# 1-Schematic_Levitator_v2.net
KiCad netlist of a schematic drawn in EasyEDA
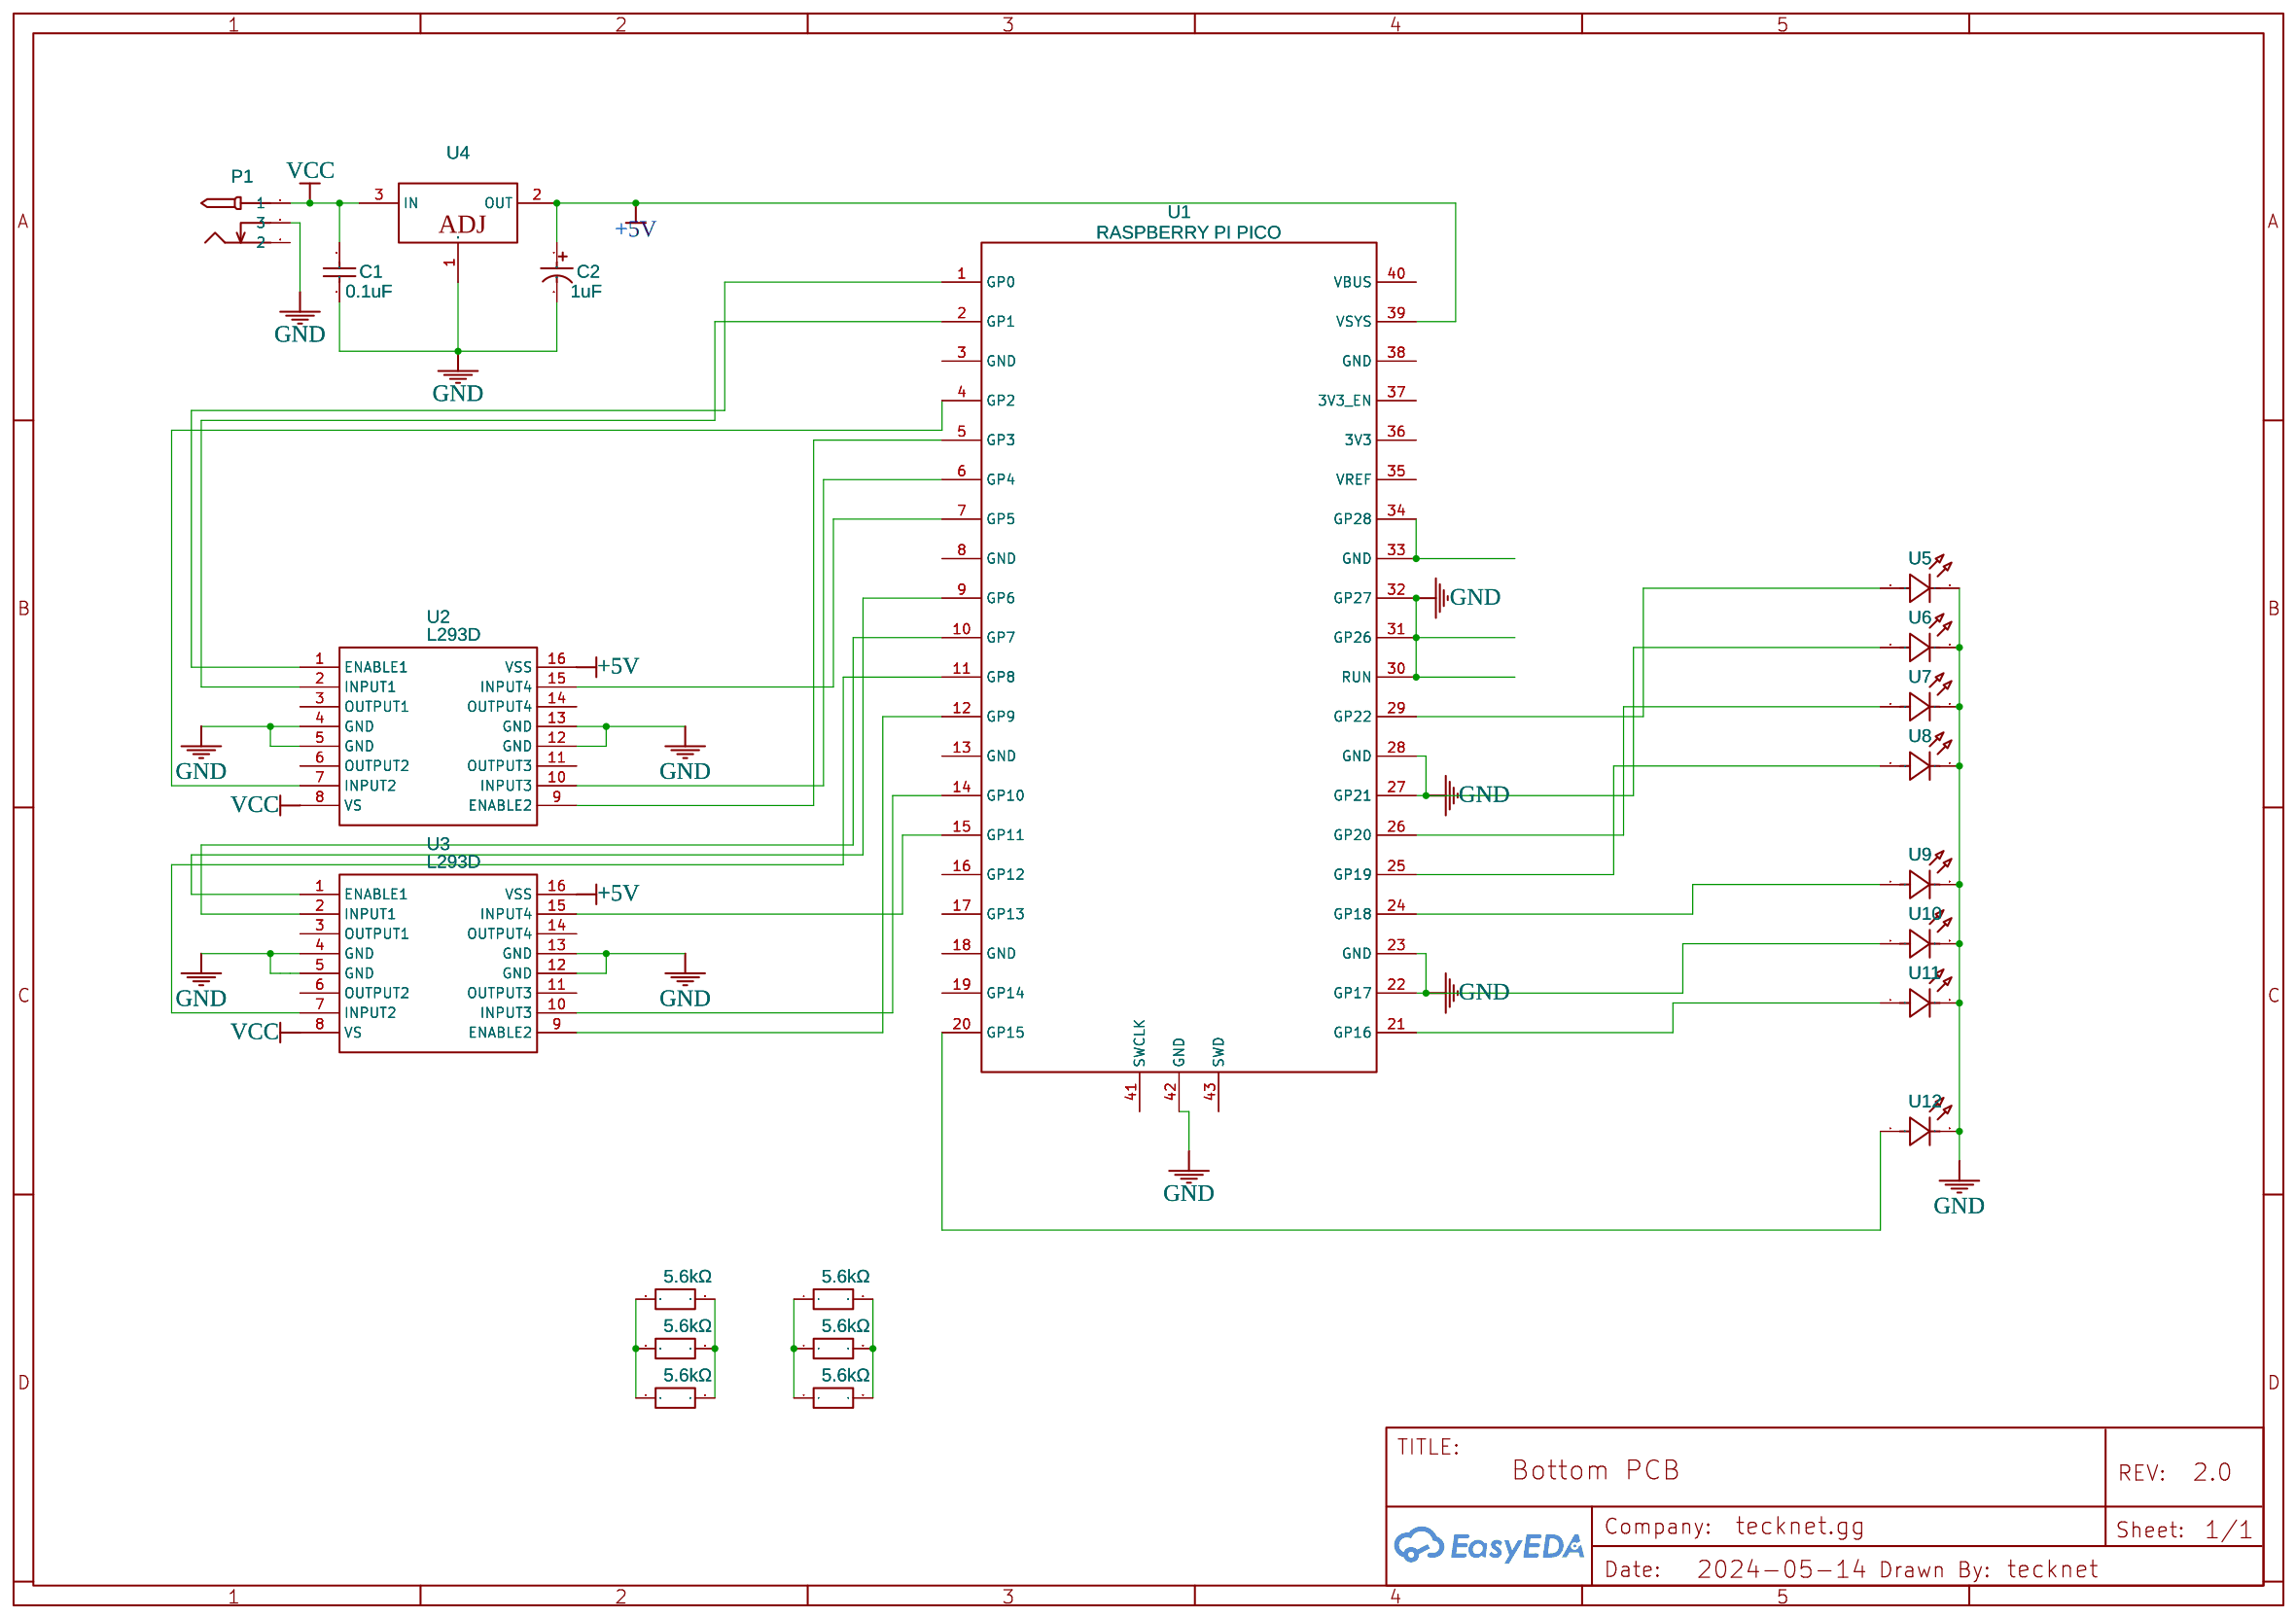
[diagram p0: Bottom PCB]
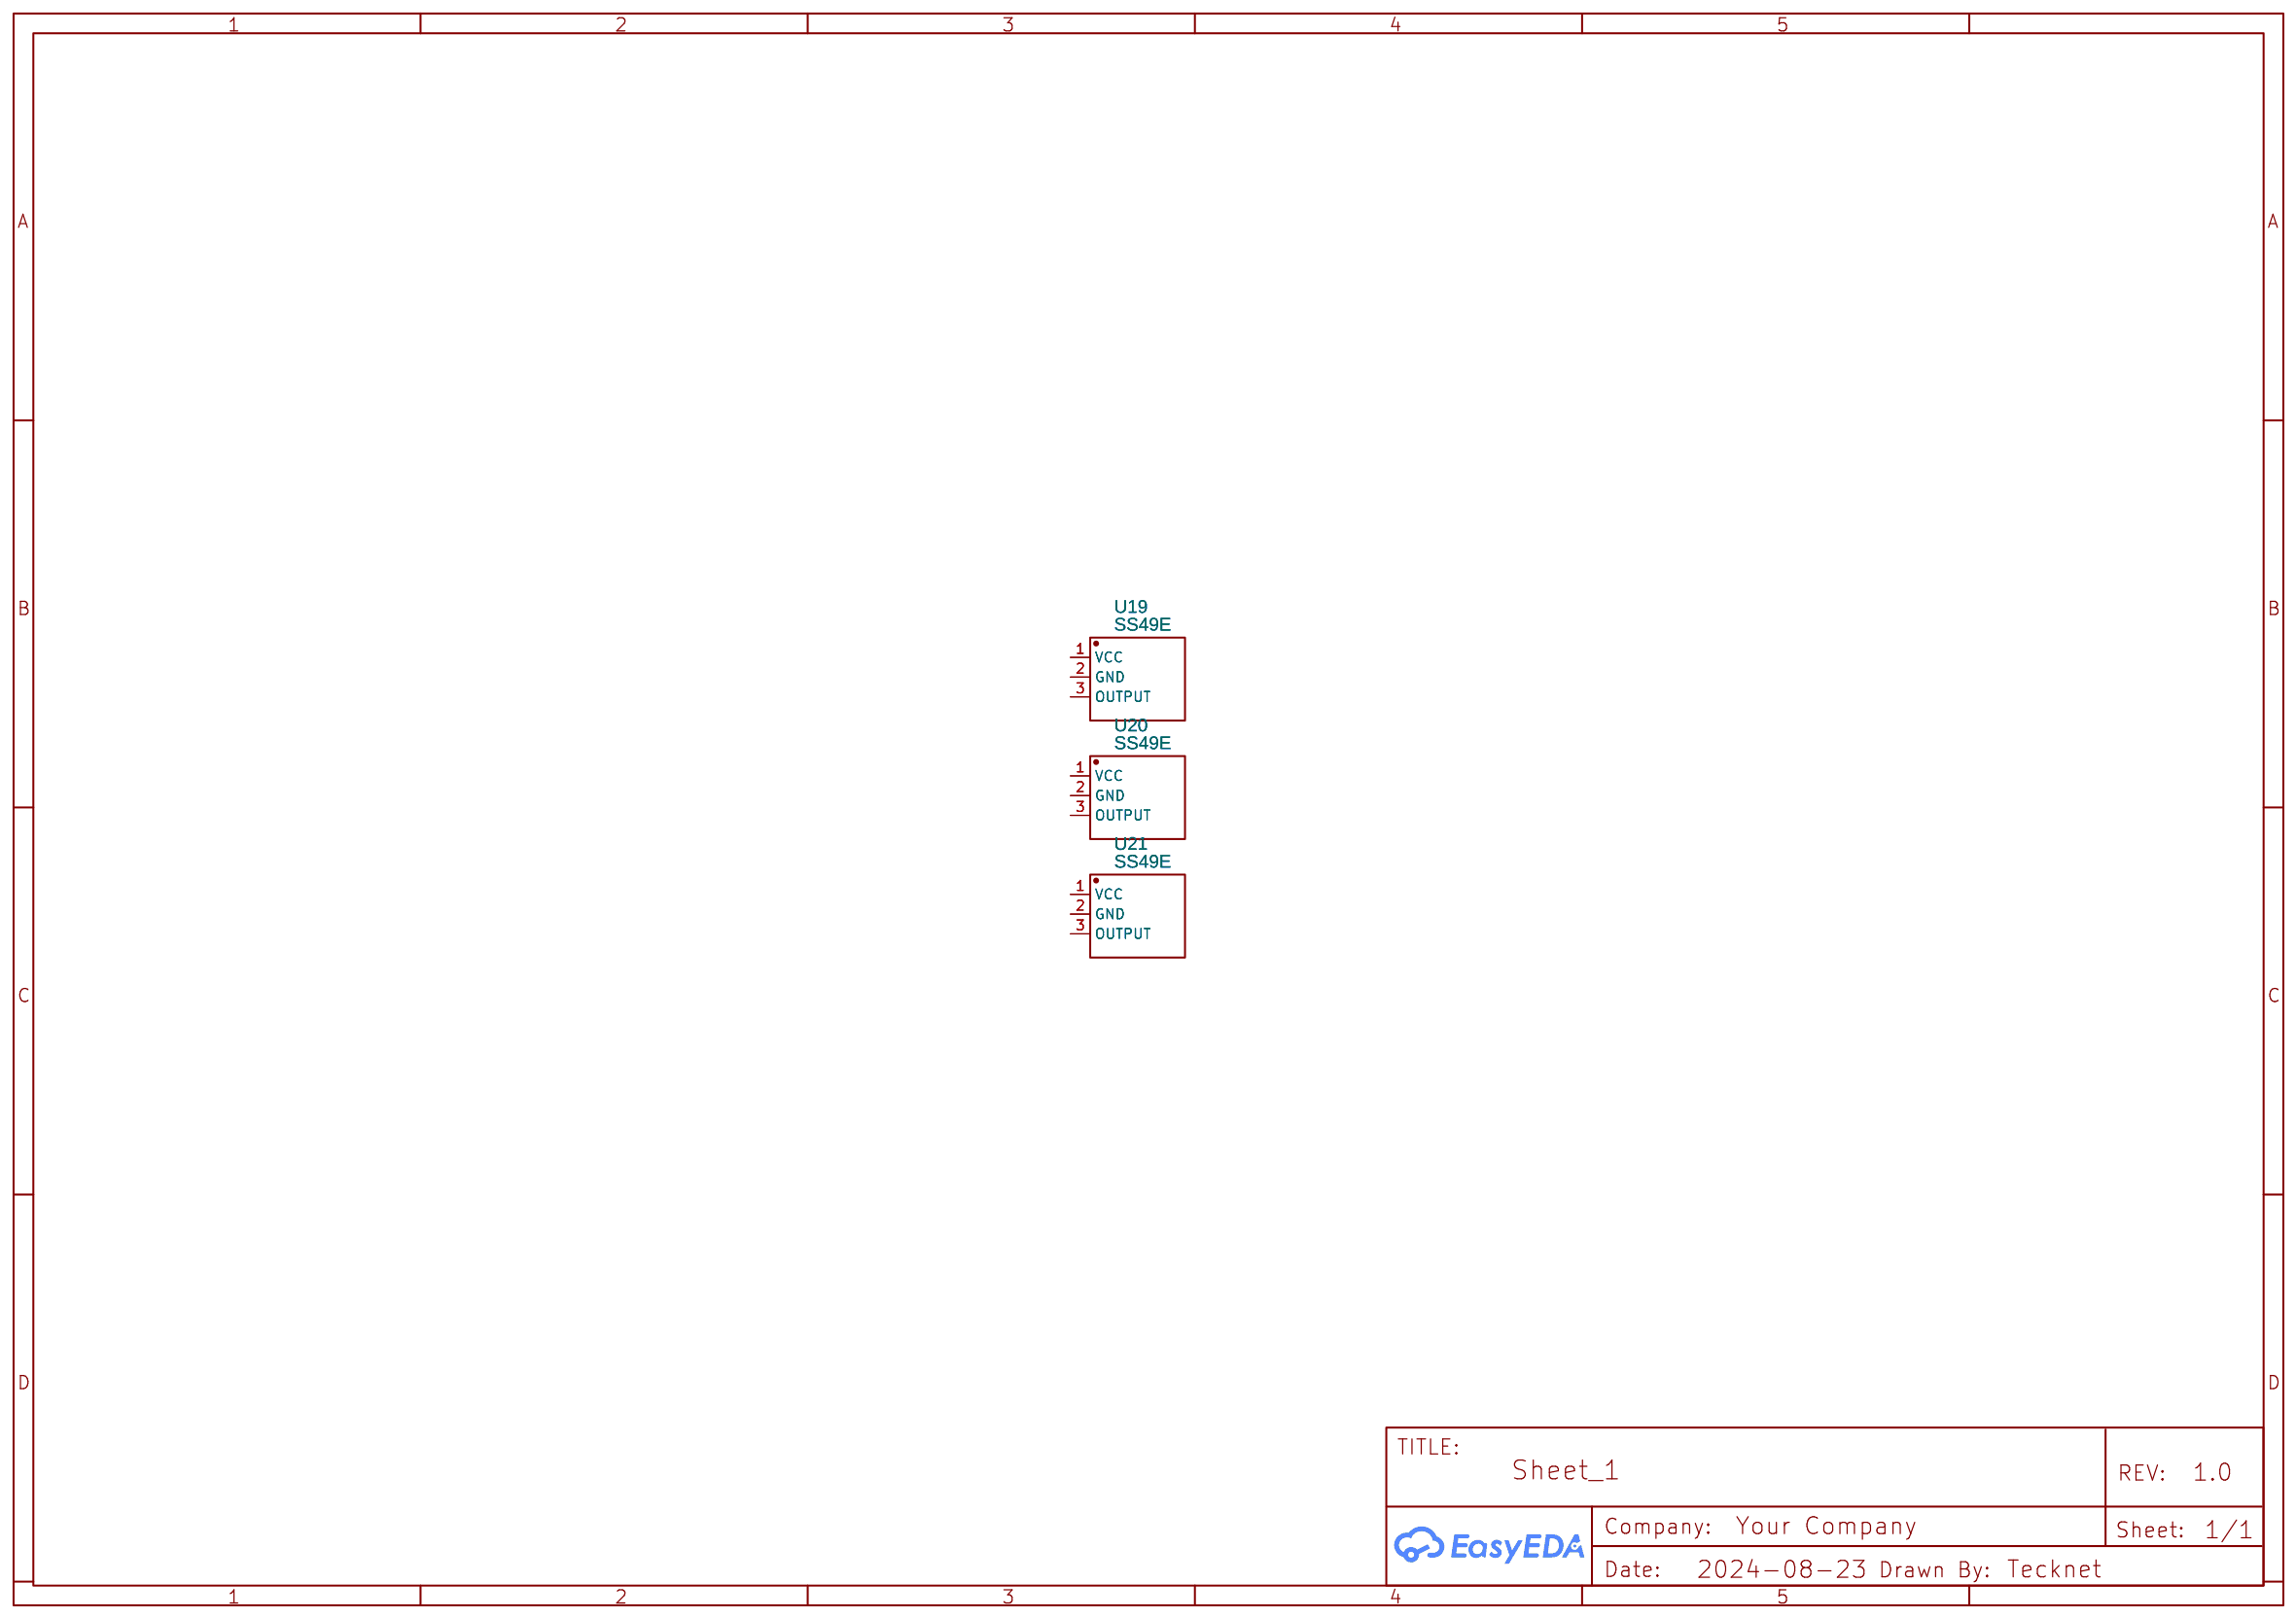
[diagram p1: Sheet_1]

(export (version "E")
  (design (tool "Eeschema 10.0.6"))
  (components
    (comp (ref "C1")
      (value "0.1uF")
      (fields (field (name "Manufacturer Part") "CT4-0805Y104M500") (field (name "Manufacturer") "LCSC"))
      (libsource (lib "") (part "CERAMIC CAPACITOR 100NF"))
    )
    (comp (ref "C2")
      (value "1uF")
      (fields
        (field (name "Manufacturer Part") "KM105M400E12RR0VH2FP0")
        (field (name "Manufacturer") "CX(承兴)")
      )
      (libsource (lib "") (part "1uF 400V 6.3*12"))
    )
    (comp (ref "P1") (value "BARREL POWER JACK 2.1MM") (libsource (lib "") (part "BARREL POWER JACK 2.1MM")))
    (comp (ref "U1")
      (value "RASPBERRY PI PICO")
      (fields (field (name "Manufacturer Part") "Raspberry Pi Pico"))
      (libsource (lib "") (part "RASPBERRY PI PICO"))
    )
    (comp (ref "U2")
      (value "L293D")
      (fields (field (name "Manufacturer") "ST(意法半导体)"))
      (libsource (lib "") (part "L293D"))
    )
    (comp (ref "U3")
      (value "L293D")
      (fields (field (name "Manufacturer") "ST(意法半导体)"))
      (libsource (lib "") (part "L293D"))
    )
    (comp (ref "U4")
      (value "LM317T_C2976492")
      (fields (field (name "Manufacturer Part") "LM317T") (field (name "Manufacturer") "ISC(无锡固电)"))
      (libsource (lib "") (part "LM317T_C2976492"))
    )
    (comp (ref "U5") (value "L240CTZ0G3MM") (libsource (lib "") (part "L240CTZ0G3MM")))
    (comp (ref "U6") (value "L240CTZ0G3MM") (libsource (lib "") (part "L240CTZ0G3MM")))
    (comp (ref "U7") (value "L240CTZ0G3MM") (libsource (lib "") (part "L240CTZ0G3MM")))
    (comp (ref "U8") (value "L240CTZ0G3MM") (libsource (lib "") (part "L240CTZ0G3MM")))
    (comp (ref "U9") (value "L240CTZ0G3MM") (libsource (lib "") (part "L240CTZ0G3MM")))
    (comp (ref "U10") (value "L240CTZ0G3MM") (libsource (lib "") (part "L240CTZ0G3MM")))
    (comp (ref "U11") (value "L240CTZ0G3MM") (libsource (lib "") (part "L240CTZ0G3MM")))
    (comp (ref "U12") (value "L240CTZ0G3MM") (libsource (lib "") (part "L240CTZ0G3MM")))
    (comp (ref "U13")
      (value "5.6kΩ")
      (fields
        (field (name "Manufacturer Part") "CF14JT5K60")
        (field (name "Manufacturer") "SEI(Stackpole Electronics Inc.)")
      )
      (libsource (lib "") (part "CF14JT5K60"))
    )
    (comp (ref "U14")
      (value "5.6kΩ")
      (fields
        (field (name "Manufacturer Part") "CF14JT5K60")
        (field (name "Manufacturer") "SEI(Stackpole Electronics Inc.)")
      )
      (libsource (lib "") (part "CF14JT5K60"))
    )
    (comp (ref "U15")
      (value "5.6kΩ")
      (fields
        (field (name "Manufacturer Part") "CF14JT5K60")
        (field (name "Manufacturer") "SEI(Stackpole Electronics Inc.)")
      )
      (libsource (lib "") (part "CF14JT5K60"))
    )
    (comp (ref "U16")
      (value "5.6kΩ")
      (fields
        (field (name "Manufacturer Part") "CF14JT5K60")
        (field (name "Manufacturer") "SEI(Stackpole Electronics Inc.)")
      )
      (libsource (lib "") (part "CF14JT5K60"))
    )
    (comp (ref "U17")
      (value "5.6kΩ")
      (fields
        (field (name "Manufacturer Part") "CF14JT5K60")
        (field (name "Manufacturer") "SEI(Stackpole Electronics Inc.)")
      )
      (libsource (lib "") (part "CF14JT5K60"))
    )
    (comp (ref "U18")
      (value "5.6kΩ")
      (fields
        (field (name "Manufacturer Part") "CF14JT5K60")
        (field (name "Manufacturer") "SEI(Stackpole Electronics Inc.)")
      )
      (libsource (lib "") (part "CF14JT5K60"))
    )
    (comp (ref "U19")
      (value "SS49E")
      (fields (field (name "Manufacturer") "Honeywell(霍尼韦尔)"))
      (libsource (lib "") (part "SS49E"))
    )
    (comp (ref "U20")
      (value "SS49E")
      (fields (field (name "Manufacturer") "Honeywell(霍尼韦尔)"))
      (libsource (lib "") (part "SS49E"))
    )
    (comp (ref "U21")
      (value "SS49E")
      (fields (field (name "Manufacturer") "Honeywell(霍尼韦尔)"))
      (libsource (lib "") (part "SS49E"))
    )
  )
  (nets
    (net (code "1") (name "+5V") (class "Default")
      (node (ref "C2") (pin "1") (pinfunction "1_1") (pintype "input"))
      (node (ref "U1") (pin "39") (pinfunction "VSYS_39") (pintype "unspecified"))
      (node (ref "U2") (pin "16") (pinfunction "VSS_16") (pintype "unspecified"))
      (node (ref "U3") (pin "16") (pinfunction "VSS_16") (pintype "unspecified"))
      (node (ref "U4") (pin "2") (pinfunction "OUT_2") (pintype "passive"))
    )
    (net (code "2") (name "GND") (class "Default")
      (node (ref "C1") (pin "1") (pinfunction "1_1") (pintype "input"))
      (node (ref "C2") (pin "2") (pinfunction "2_2") (pintype "input"))
      (node (ref "P1") (pin "3") (pinfunction "3_3") (pintype "unspecified"))
      (node (ref "U1") (pin "22") (pinfunction "GP17_22") (pintype "unspecified"))
      (node (ref "U1") (pin "23") (pinfunction "GND_23") (pintype "unspecified"))
      (node (ref "U1") (pin "27") (pinfunction "GP21_27") (pintype "unspecified"))
      (node (ref "U1") (pin "28") (pinfunction "GND_28") (pintype "unspecified"))
      (node (ref "U1") (pin "30") (pinfunction "RUN_30") (pintype "unspecified"))
      (node (ref "U1") (pin "31") (pinfunction "GP26_31") (pintype "unspecified"))
      (node (ref "U1") (pin "32") (pinfunction "GP27_32") (pintype "unspecified"))
      (node (ref "U1") (pin "42") (pinfunction "GND_42") (pintype "unspecified"))
      (node (ref "U10") (pin "1") (pinfunction "A_1") (pintype "unspecified"))
      (node (ref "U10") (pin "2") (pinfunction "K_2") (pintype "unspecified"))
      (node (ref "U11") (pin "2") (pinfunction "K_2") (pintype "unspecified"))
      (node (ref "U12") (pin "2") (pinfunction "K_2") (pintype "unspecified"))
      (node (ref "U2") (pin "12") (pinfunction "GND_12") (pintype "unspecified"))
      (node (ref "U2") (pin "13") (pinfunction "GND_13") (pintype "unspecified"))
      (node (ref "U2") (pin "4") (pinfunction "GND_4") (pintype "unspecified"))
      (node (ref "U2") (pin "5") (pinfunction "GND_5") (pintype "unspecified"))
      (node (ref "U3") (pin "12") (pinfunction "GND_12") (pintype "unspecified"))
      (node (ref "U3") (pin "13") (pinfunction "GND_13") (pintype "unspecified"))
      (node (ref "U3") (pin "4") (pinfunction "GND_4") (pintype "unspecified"))
      (node (ref "U3") (pin "5") (pinfunction "GND_5") (pintype "unspecified"))
      (node (ref "U4") (pin "1") (pinfunction "ADJ_1") (pintype "unspecified"))
      (node (ref "U5") (pin "2") (pinfunction "K_2") (pintype "unspecified"))
      (node (ref "U6") (pin "1") (pinfunction "A_1") (pintype "unspecified"))
      (node (ref "U6") (pin "2") (pinfunction "K_2") (pintype "unspecified"))
      (node (ref "U7") (pin "2") (pinfunction "K_2") (pintype "unspecified"))
      (node (ref "U8") (pin "2") (pinfunction "K_2") (pintype "unspecified"))
      (node (ref "U9") (pin "2") (pinfunction "K_2") (pintype "unspecified"))
    )
    (net (code "3") (name "Net-(U1-GP0)") (class "Default")
      (node (ref "U1") (pin "1") (pinfunction "GP0_1") (pintype "unspecified"))
      (node (ref "U2") (pin "1") (pinfunction "ENABLE1_1") (pintype "unspecified"))
    )
    (net (code "4") (name "Net-(U1-GP1)") (class "Default")
      (node (ref "U1") (pin "2") (pinfunction "GP1_2") (pintype "unspecified"))
      (node (ref "U2") (pin "2") (pinfunction "INPUT1_2") (pintype "unspecified"))
    )
    (net (code "5") (name "Net-(U1-GP2)") (class "Default")
      (node (ref "U1") (pin "4") (pinfunction "GP2_4") (pintype "unspecified"))
      (node (ref "U2") (pin "7") (pinfunction "INPUT2_7") (pintype "unspecified"))
    )
    (net (code "6") (name "Net-(U1-GP3)") (class "Default")
      (node (ref "U1") (pin "5") (pinfunction "GP3_5") (pintype "unspecified"))
      (node (ref "U2") (pin "9") (pinfunction "ENABLE2_9") (pintype "unspecified"))
    )
    (net (code "7") (name "Net-(U1-GP4)") (class "Default")
      (node (ref "U1") (pin "6") (pinfunction "GP4_6") (pintype "unspecified"))
      (node (ref "U2") (pin "10") (pinfunction "INPUT3_10") (pintype "unspecified"))
    )
    (net (code "8") (name "Net-(U1-GP5)") (class "Default")
      (node (ref "U1") (pin "7") (pinfunction "GP5_7") (pintype "unspecified"))
      (node (ref "U2") (pin "15") (pinfunction "INPUT4_15") (pintype "unspecified"))
    )
    (net (code "9") (name "Net-(U1-GP6)") (class "Default")
      (node (ref "U1") (pin "9") (pinfunction "GP6_9") (pintype "unspecified"))
      (node (ref "U3") (pin "1") (pinfunction "ENABLE1_1") (pintype "unspecified"))
    )
    (net (code "10") (name "Net-(U1-GP7)") (class "Default")
      (node (ref "U1") (pin "10") (pinfunction "GP7_10") (pintype "unspecified"))
      (node (ref "U3") (pin "2") (pinfunction "INPUT1_2") (pintype "unspecified"))
    )
    (net (code "11") (name "Net-(U1-GP8)") (class "Default")
      (node (ref "U1") (pin "11") (pinfunction "GP8_11") (pintype "unspecified"))
      (node (ref "U3") (pin "7") (pinfunction "INPUT2_7") (pintype "unspecified"))
    )
    (net (code "12") (name "Net-(U1-GP9)") (class "Default")
      (node (ref "U1") (pin "12") (pinfunction "GP9_12") (pintype "unspecified"))
      (node (ref "U3") (pin "9") (pinfunction "ENABLE2_9") (pintype "unspecified"))
    )
    (net (code "13") (name "Net-(U1-GP10)") (class "Default")
      (node (ref "U1") (pin "14") (pinfunction "GP10_14") (pintype "unspecified"))
      (node (ref "U3") (pin "10") (pinfunction "INPUT3_10") (pintype "unspecified"))
    )
    (net (code "14") (name "Net-(U1-GP11)") (class "Default")
      (node (ref "U1") (pin "15") (pinfunction "GP11_15") (pintype "unspecified"))
      (node (ref "U3") (pin "15") (pinfunction "INPUT4_15") (pintype "unspecified"))
    )
    (net (code "15") (name "Net-(U1-GP15)") (class "Default")
      (node (ref "U1") (pin "20") (pinfunction "GP15_20") (pintype "unspecified"))
      (node (ref "U12") (pin "1") (pinfunction "A_1") (pintype "unspecified"))
    )
    (net (code "16") (name "Net-(U1-GP16)") (class "Default")
      (node (ref "U1") (pin "21") (pinfunction "GP16_21") (pintype "unspecified"))
      (node (ref "U11") (pin "1") (pinfunction "A_1") (pintype "unspecified"))
    )
    (net (code "17") (name "Net-(U1-GP18)") (class "Default")
      (node (ref "U1") (pin "24") (pinfunction "GP18_24") (pintype "unspecified"))
      (node (ref "U9") (pin "1") (pinfunction "A_1") (pintype "unspecified"))
    )
    (net (code "18") (name "Net-(U1-GP19)") (class "Default")
      (node (ref "U1") (pin "25") (pinfunction "GP19_25") (pintype "unspecified"))
      (node (ref "U8") (pin "1") (pinfunction "A_1") (pintype "unspecified"))
    )
    (net (code "19") (name "Net-(U1-GP20)") (class "Default")
      (node (ref "U1") (pin "26") (pinfunction "GP20_26") (pintype "unspecified"))
      (node (ref "U7") (pin "1") (pinfunction "A_1") (pintype "unspecified"))
    )
    (net (code "20") (name "Net-(U1-GP22)") (class "Default")
      (node (ref "U1") (pin "29") (pinfunction "GP22_29") (pintype "unspecified"))
      (node (ref "U5") (pin "1") (pinfunction "A_1") (pintype "unspecified"))
    )
    (net (code "21") (name "Net-(U1-GP28)") (class "Default")
      (node (ref "U1") (pin "33") (pinfunction "GND_33") (pintype "unspecified"))
      (node (ref "U1") (pin "34") (pinfunction "GP28_34") (pintype "unspecified"))
    )
    (net (code "22") (name "Net-(U13-Pad1)") (class "Default")
      (node (ref "U13") (pin "1") (pinfunction "1_1") (pintype "unspecified"))
      (node (ref "U14") (pin "1") (pinfunction "1_1") (pintype "unspecified"))
      (node (ref "U15") (pin "1") (pinfunction "1_1") (pintype "unspecified"))
    )
    (net (code "23") (name "Net-(U13-Pad2)") (class "Default")
      (node (ref "U13") (pin "2") (pinfunction "2_2") (pintype "unspecified"))
      (node (ref "U14") (pin "2") (pinfunction "2_2") (pintype "unspecified"))
      (node (ref "U15") (pin "2") (pinfunction "2_2") (pintype "unspecified"))
    )
    (net (code "24") (name "Net-(U16-Pad1)") (class "Default")
      (node (ref "U16") (pin "1") (pinfunction "1_1") (pintype "unspecified"))
      (node (ref "U17") (pin "1") (pinfunction "1_1") (pintype "unspecified"))
      (node (ref "U18") (pin "1") (pinfunction "1_1") (pintype "unspecified"))
    )
    (net (code "25") (name "Net-(U16-Pad2)") (class "Default")
      (node (ref "U16") (pin "2") (pinfunction "2_2") (pintype "unspecified"))
      (node (ref "U17") (pin "2") (pinfunction "2_2") (pintype "unspecified"))
      (node (ref "U18") (pin "2") (pinfunction "2_2") (pintype "unspecified"))
    )
    (net (code "26") (name "VCC") (class "Default")
      (node (ref "C1") (pin "2") (pinfunction "2_2") (pintype "input"))
      (node (ref "P1") (pin "1") (pinfunction "1_1") (pintype "unspecified"))
      (node (ref "U2") (pin "8") (pinfunction "VS_8") (pintype "unspecified"))
      (node (ref "U3") (pin "8") (pinfunction "VS_8") (pintype "unspecified"))
      (node (ref "U4") (pin "3") (pinfunction "IN_3") (pintype "passive"))
    )
    (net (code "27") (name "unconnected-(P1-Pad2)") (class "Default")
      (node (ref "P1") (pin "2") (pinfunction "2_2") (pintype "unspecified"))
    )
    (net (code "28") (name "unconnected-(U1-3V3-Pad36)") (class "Default")
      (node (ref "U1") (pin "36") (pinfunction "3V3_36") (pintype "unspecified"))
    )
    (net (code "29") (name "unconnected-(U1-3V3_EN-Pad37)") (class "Default")
      (node (ref "U1") (pin "37") (pinfunction "3V3_EN_37") (pintype "unspecified"))
    )
    (net (code "30") (name "unconnected-(U1-GND-Pad3)") (class "Default")
      (node (ref "U1") (pin "3") (pinfunction "GND_3") (pintype "unspecified"))
    )
    (net (code "31") (name "unconnected-(U1-GND-Pad8)") (class "Default")
      (node (ref "U1") (pin "8") (pinfunction "GND_8") (pintype "unspecified"))
    )
    (net (code "32") (name "unconnected-(U1-GND-Pad13)") (class "Default")
      (node (ref "U1") (pin "13") (pinfunction "GND_13") (pintype "unspecified"))
    )
    (net (code "33") (name "unconnected-(U1-GND-Pad18)") (class "Default")
      (node (ref "U1") (pin "18") (pinfunction "GND_18") (pintype "unspecified"))
    )
    (net (code "34") (name "unconnected-(U1-GND-Pad38)") (class "Default")
      (node (ref "U1") (pin "38") (pinfunction "GND_38") (pintype "unspecified"))
    )
    (net (code "35") (name "unconnected-(U1-GP12-Pad16)") (class "Default")
      (node (ref "U1") (pin "16") (pinfunction "GP12_16") (pintype "unspecified"))
    )
    (net (code "36") (name "unconnected-(U1-GP13-Pad17)") (class "Default")
      (node (ref "U1") (pin "17") (pinfunction "GP13_17") (pintype "unspecified"))
    )
    (net (code "37") (name "unconnected-(U1-GP14-Pad19)") (class "Default")
      (node (ref "U1") (pin "19") (pinfunction "GP14_19") (pintype "unspecified"))
    )
    (net (code "38") (name "unconnected-(U1-SWCLK-Pad41)") (class "Default")
      (node (ref "U1") (pin "41") (pinfunction "SWCLK_41") (pintype "unspecified"))
    )
    (net (code "39") (name "unconnected-(U1-SWD-Pad43)") (class "Default")
      (node (ref "U1") (pin "43") (pinfunction "SWD_43") (pintype "unspecified"))
    )
    (net (code "40") (name "unconnected-(U1-VBUS-Pad40)") (class "Default")
      (node (ref "U1") (pin "40") (pinfunction "VBUS_40") (pintype "unspecified"))
    )
    (net (code "41") (name "unconnected-(U1-VREF-Pad35)") (class "Default")
      (node (ref "U1") (pin "35") (pinfunction "VREF_35") (pintype "unspecified"))
    )
    (net (code "42") (name "unconnected-(U2-OUTPUT1-Pad3)") (class "Default")
      (node (ref "U2") (pin "3") (pinfunction "OUTPUT1_3") (pintype "unspecified"))
    )
    (net (code "43") (name "unconnected-(U2-OUTPUT2-Pad6)") (class "Default")
      (node (ref "U2") (pin "6") (pinfunction "OUTPUT2_6") (pintype "unspecified"))
    )
    (net (code "44") (name "unconnected-(U2-OUTPUT3-Pad11)") (class "Default")
      (node (ref "U2") (pin "11") (pinfunction "OUTPUT3_11") (pintype "unspecified"))
    )
    (net (code "45") (name "unconnected-(U2-OUTPUT4-Pad14)") (class "Default")
      (node (ref "U2") (pin "14") (pinfunction "OUTPUT4_14") (pintype "unspecified"))
    )
    (net (code "46") (name "unconnected-(U3-OUTPUT1-Pad3)") (class "Default")
      (node (ref "U3") (pin "3") (pinfunction "OUTPUT1_3") (pintype "unspecified"))
    )
    (net (code "47") (name "unconnected-(U3-OUTPUT2-Pad6)") (class "Default")
      (node (ref "U3") (pin "6") (pinfunction "OUTPUT2_6") (pintype "unspecified"))
    )
    (net (code "48") (name "unconnected-(U3-OUTPUT3-Pad11)") (class "Default")
      (node (ref "U3") (pin "11") (pinfunction "OUTPUT3_11") (pintype "unspecified"))
    )
    (net (code "49") (name "unconnected-(U3-OUTPUT4-Pad14)") (class "Default")
      (node (ref "U3") (pin "14") (pinfunction "OUTPUT4_14") (pintype "unspecified"))
    )
    (net (code "50") (name "unconnected-(U19-GND-Pad2)") (class "Default")
      (node (ref "U19") (pin "2") (pinfunction "GND_2") (pintype "unspecified"))
    )
    (net (code "51") (name "unconnected-(U19-OUTPUT-Pad3)") (class "Default")
      (node (ref "U19") (pin "3") (pinfunction "OUTPUT_3") (pintype "unspecified"))
    )
    (net (code "52") (name "unconnected-(U19-VCC-Pad1)") (class "Default")
      (node (ref "U19") (pin "1") (pinfunction "VCC_1") (pintype "unspecified"))
    )
    (net (code "53") (name "unconnected-(U20-GND-Pad2)") (class "Default")
      (node (ref "U20") (pin "2") (pinfunction "GND_2") (pintype "unspecified"))
    )
    (net (code "54") (name "unconnected-(U20-OUTPUT-Pad3)") (class "Default")
      (node (ref "U20") (pin "3") (pinfunction "OUTPUT_3") (pintype "unspecified"))
    )
    (net (code "55") (name "unconnected-(U20-VCC-Pad1)") (class "Default")
      (node (ref "U20") (pin "1") (pinfunction "VCC_1") (pintype "unspecified"))
    )
    (net (code "56") (name "unconnected-(U21-GND-Pad2)") (class "Default")
      (node (ref "U21") (pin "2") (pinfunction "GND_2") (pintype "unspecified"))
    )
    (net (code "57") (name "unconnected-(U21-OUTPUT-Pad3)") (class "Default")
      (node (ref "U21") (pin "3") (pinfunction "OUTPUT_3") (pintype "unspecified"))
    )
    (net (code "58") (name "unconnected-(U21-VCC-Pad1)") (class "Default")
      (node (ref "U21") (pin "1") (pinfunction "VCC_1") (pintype "unspecified"))
    )
  )
)
